# USB.net
KiCad netlist of a schematic drawn in Altium Designer
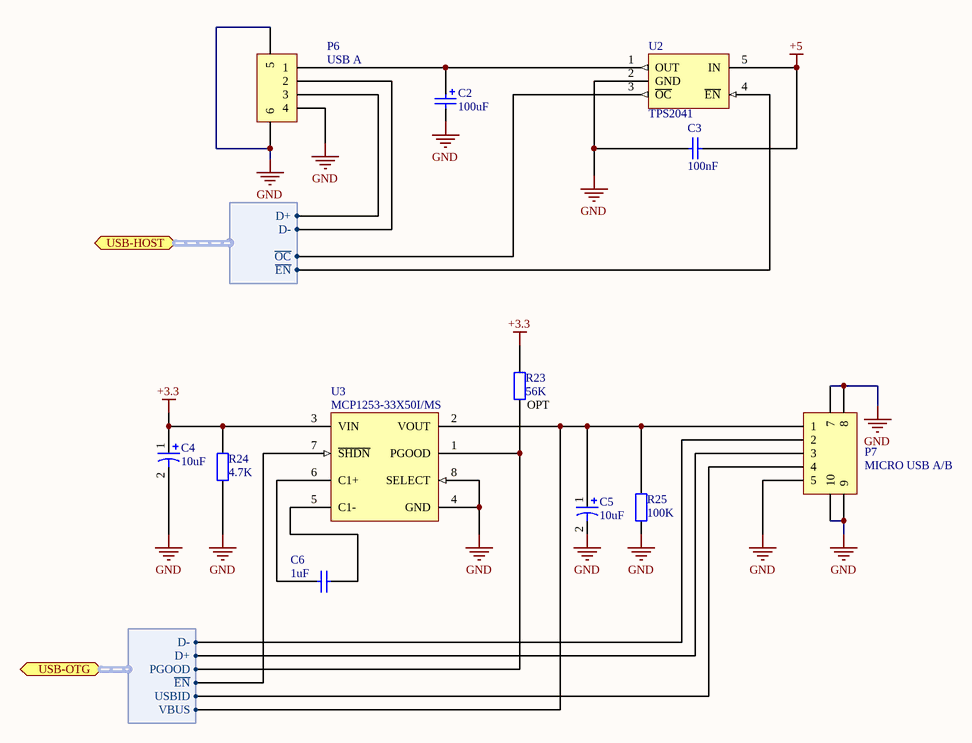
[diagram p0: USB.SchDoc]

(export (version "E")
  (design (tool "Eeschema 10.0.6"))
  (components
    (comp (ref "C2")
      (value "100uF")
      (footprint "Kemet_63")
      (description "Polarized Capacitor")
      (fields
        (field (name "MANUFACTURER") "EPCOS")
        (field (name "MANUFACTURER PART NUMBER") "B41142A4107M")
        (field (name "HAUTEUR") "7.7")
        (field (name "LONGUEUR/HAUTEUR") "7.7")
      )
      (libsource (lib "BRA") (part "Cap Pol 100uF"))
    )
    (comp (ref "C3")
      (value "100nF")
      (footprint "C0805")
      (description "Capacitor")
      (fields
        (field (name "MANUFACTURER") "MULTICOMP")
        (field (name "MANUFACTURER PART NUMBER") "MCCA000296")
      )
      (libsource (lib "BRA") (part "Cap 0805 100nF"))
    )
    (comp (ref "C4")
      (value "10uF")
      (footprint "SYLANN:KEMET_4")
      (description "Polarized Capacitor")
      (fields
        (field (name "MANUFACTURER") "KEMET")
        (field (name "MANUFACTURER PART NUMBER") "EXV106M025A9BAA")
      )
      (libsource (lib "Miscellaneous Devices") (part "Cap Pol1"))
    )
    (comp (ref "C5")
      (value "10uF")
      (footprint "SYLANN:KEMET_4")
      (description "Polarized Capacitor")
      (fields
        (field (name "MANUFACTURER") "KEMET")
        (field (name "MANUFACTURER PART NUMBER") "EXV106M025A9BAA")
      )
      (libsource (lib "Miscellaneous Devices") (part "Cap Pol1"))
    )
    (comp (ref "C6")
      (value "1uF")
      (footprint "C0805")
      (description "Capacitor")
      (fields
        (field (name "MANUFACTURER") "MULTICOMP")
        (field (name "MANUFACTURER PART NUMBER") "MCCA000549")
      )
      (libsource (lib "BRA") (part "Cap 0805 1uF"))
    )
    (comp (ref "P6")
      (value "USB A")
      (footprint "USB  2410 06")
      (description "USB 2.0 Connector A")
      (fields (field (name "MANUFACTURER") "LUMBERG") (field (name "MANUFACTURER PART NUMBER") "2410 06"))
      (libsource (lib "MAIN BOARD CERES") (part "Header 4_1"))
    )
    (comp (ref "P7")
      (value "MICRO USB A/B")
      (footprint "USB FCI 10104111")
      (description "Header, 5-Pin")
      (fields
        (field (name "MANUFACTURER") "FCI")
        (field (name "MANUFACTURER PART NUMBER") "10104111-0001LF")
        (field (name "PUBLISHER") "Altium Limited")
      )
      (libsource (lib "MAIN BOARD CERES") (part "Header 5"))
    )
    (comp (ref "R23")
      (value "56K")
      (footprint "R0805")
      (description "Resistor")
      (fields
        (field (name "MANUFACTURER") "MULTICOMP")
        (field (name "MANUFACTURER PART NUMBER") "MC0.1W08051%56KFR")
      )
      (libsource (lib "BRA") (part "Resistor 0805 56K"))
    )
    (comp (ref "R24")
      (value "4.7K")
      (footprint "R0805")
      (description "Resistor")
      (fields
        (field (name "MANUFACTURER") "MULTICOMP")
        (field (name "MANUFACTURER PART NUMBER") "MC01W080514K7")
      )
      (libsource (lib "BRA") (part "Resistor 0805 4.7K"))
    )
    (comp (ref "R25")
      (value "100K")
      (footprint "R0805")
      (description "Resistor")
      (fields
        (field (name "MANUFACTURER") "MULTICOMP")
        (field (name "MANUFACTURER PART NUMBER") "MC0.1W08051%100KFR")
      )
      (libsource (lib "BRA") (part "Resistor 0805 100K"))
    )
    (comp (ref "U2")
      (value "TPS2041")
      (footprint "SOT23-5")
      (description "Power DIST Switch")
      (fields
        (field (name "MANUFACTURER") "TEXAS INSTRUMENTS")
        (field (name "MANUFACTURER PART NUMBER") "TPS2041BDBVR")
      )
      (libsource (lib "BRA") (part "TPS2041-DBV"))
    )
    (comp (ref "U3")
      (value "MCP1253-33X50I/MS")
      (footprint "MSOP-8")
      (description "Low Noise, Positive-Regulated Charge Pump, 1MHz, Fixed Output, 8-Pin MSOP, Industrial Temperature")
      (fields (field (name "MANUFACTURER") "MICROCHIP"))
      (libsource (lib "Microchip Power Mgt Charge Pump") (part "MCP1253-33X50I/MS"))
    )
  )
  (nets
    (net (code "3") (name "+3.3") (class "Default")
      (node (ref "C4") (pin "1") (pinfunction "1_1") (pintype "passive"))
      (node (ref "R23") (pin "1") (pinfunction "1_1") (pintype "passive"))
      (node (ref "R24") (pin "2") (pinfunction "2_2") (pintype "passive"))
      (node (ref "U3") (pin "3") (pinfunction "VIN_3") (pintype "power_in"))
    )
    (net (code "4") (name "+5") (class "Default")
      (node (ref "C3") (pin "1") (pinfunction "1_1") (pintype "passive"))
      (node (ref "U2") (pin "5") (pinfunction "IN_5") (pintype "power_in"))
    )
    (net (code "5") (name "/PGOOD") (class "Default")
      (node (ref "R23") (pin "2") (pinfunction "2_2") (pintype "passive"))
      (node (ref "U3") (pin "1") (pinfunction "PGOOD_1") (pintype "open_collector"))
    )
    (net (code "6") (name "/USBID") (class "Default")
      (node (ref "P7") (pin "4") (pinfunction "4_4") (pintype "passive"))
    )
    (net (code "7") (name "/VBUS") (class "Default")
      (node (ref "C5") (pin "1") (pinfunction "1_1") (pintype "passive"))
      (node (ref "P7") (pin "1") (pinfunction "1_1") (pintype "passive"))
      (node (ref "R25") (pin "2") (pinfunction "2_2") (pintype "passive"))
      (node (ref "U3") (pin "2") (pinfunction "VOUT_2") (pintype "power_in"))
    )
    (net (code "10") (name "/~{OC}") (class "Default")
      (node (ref "U2") (pin "3") (pinfunction "~{OC}_3") (pintype "output"))
    )
    (net (code "11") (name "GND") (class "Default")
      (node (ref "C2") (pin "2") (pinfunction "2_2") (pintype "passive"))
      (node (ref "C3") (pin "2") (pinfunction "2_2") (pintype "passive"))
      (node (ref "C4") (pin "2") (pinfunction "2_2") (pintype "passive"))
      (node (ref "C5") (pin "2") (pinfunction "2_2") (pintype "passive"))
      (node (ref "P6") (pin "4") (pinfunction "4_4") (pintype "passive"))
      (node (ref "P6") (pin "5") (pinfunction "5_5") (pintype "passive"))
      (node (ref "P6") (pin "6") (pinfunction "6_6") (pintype "passive"))
      (node (ref "P7") (pin "10") (pinfunction "10_10") (pintype "passive"))
      (node (ref "P7") (pin "5") (pinfunction "5_5") (pintype "passive"))
      (node (ref "P7") (pin "7") (pinfunction "7_7") (pintype "passive"))
      (node (ref "P7") (pin "8") (pinfunction "8_8") (pintype "passive"))
      (node (ref "P7") (pin "9") (pinfunction "9_9") (pintype "passive"))
      (node (ref "R24") (pin "1") (pinfunction "1_1") (pintype "passive"))
      (node (ref "R25") (pin "1") (pinfunction "1_1") (pintype "passive"))
      (node (ref "U2") (pin "2") (pinfunction "GND_2") (pintype "power_in"))
      (node (ref "U3") (pin "4") (pinfunction "GND_4") (pintype "power_in"))
      (node (ref "U3") (pin "8") (pinfunction "SELECT_8") (pintype "input"))
    )
    (net (code "12") (name "Net-(U2-OUT)") (class "Default")
      (node (ref "C2") (pin "1") (pinfunction "1_1") (pintype "passive"))
      (node (ref "P6") (pin "1") (pinfunction "1_1") (pintype "passive"))
      (node (ref "U2") (pin "1") (pinfunction "OUT_1") (pintype "output"))
    )
    (net (code "13") (name "Net-(U3-C1+)") (class "Default")
      (node (ref "C6") (pin "1") (pinfunction "1_1") (pintype "passive"))
      (node (ref "U3") (pin "6") (pinfunction "C1+_6") (pintype "passive"))
    )
    (net (code "14") (name "Net-(U3-C1-)") (class "Default")
      (node (ref "C6") (pin "2") (pinfunction "2_2") (pintype "passive"))
      (node (ref "U3") (pin "5") (pinfunction "C1-_5") (pintype "passive"))
    )
    (net (code "15") (name "unconnected-(P6-Pad2)") (class "Default")
      (node (ref "P6") (pin "2") (pinfunction "2_2") (pintype "passive"))
    )
    (net (code "16") (name "unconnected-(P6-Pad3)") (class "Default")
      (node (ref "P6") (pin "3") (pinfunction "3_3") (pintype "passive"))
    )
    (net (code "17") (name "unconnected-(P7-Pad2)") (class "Default")
      (node (ref "P7") (pin "2") (pinfunction "2_2") (pintype "passive"))
    )
    (net (code "18") (name "unconnected-(P7-Pad3)") (class "Default")
      (node (ref "P7") (pin "3") (pinfunction "3_3") (pintype "passive"))
    )
    (net (code "19") (name "unconnected-(U2-~{EN}-Pad4)") (class "Default")
      (node (ref "U2") (pin "4") (pinfunction "~{EN}_4") (pintype "input"))
    )
    (net (code "20") (name "unconnected-(U3-~{SHDN}-Pad7)") (class "Default")
      (node (ref "U3") (pin "7") (pinfunction "~{SHDN}_7") (pintype "input"))
    )
  )
)
